# transformerless_5v_AC-DC_reulator.net
KiCad netlist of a schematic drawn in EAGLE
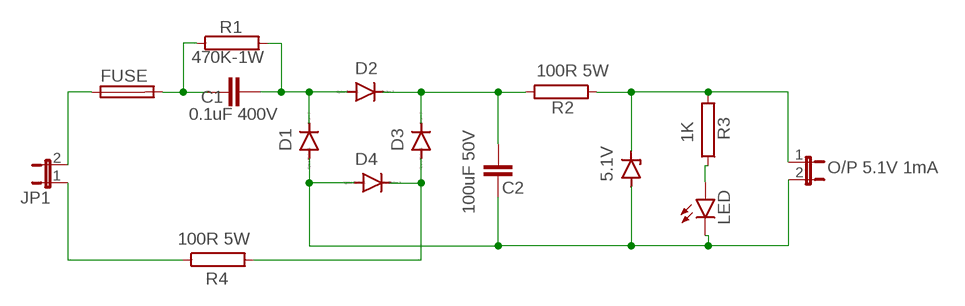
[diagram p0: schematic, sheet 1]

(export (version "E")
  (design (tool "Eeschema 10.0.6"))
  (components
    (comp (ref "C1")
      (value "0.1uF 400V")
      (footprint "eagle-import:C2.5-3")
      (libsource (lib "eagle-import") (part "C2,5-3"))
    )
    (comp (ref "C2")
      (value "100uF 50V")
      (footprint "eagle-import:C2.5-3")
      (libsource (lib "eagle-import") (part "C2,5-3"))
    )
    (comp (ref "D1")
      (value "1N4004")
      (footprint "eagle-import:DO41-10")
      (libsource (lib "eagle-import") (part "1N4004"))
    )
    (comp (ref "D2")
      (value "1N4004")
      (footprint "eagle-import:DO41-10")
      (libsource (lib "eagle-import") (part "1N4004"))
    )
    (comp (ref "D3")
      (value "1N4004")
      (footprint "eagle-import:DO41-10")
      (libsource (lib "eagle-import") (part "1N4004"))
    )
    (comp (ref "D4")
      (value "1N4004")
      (footprint "eagle-import:DO41-10")
      (libsource (lib "eagle-import") (part "1N4004"))
    )
    (comp (ref "FUSE")
      (value "GSH15")
      (footprint "eagle-import:GSH15")
      (fields (field (name "MPN") "64900001039"))
      (libsource (lib "eagle-import") (part "GSH15"))
    )
    (comp (ref "JP1")
      (value "JP1E")
      (footprint "eagle-import:JP1")
      (libsource (lib "eagle-import") (part "JP1E"))
    )
    (comp (ref "LED")
      (value "LED")
      (footprint "eagle-import:SMARTLED-TTW")
      (libsource (lib "eagle-import") (part "LED"))
    )
    (comp (ref "O/P")
      (value "O/P 5.1V 1mA")
      (footprint "eagle-import:JP1")
      (libsource (lib "eagle-import") (part "JP1E"))
    )
    (comp (ref "R1")
      (value "470K-1W")
      (footprint "eagle-import:AC01")
      (libsource (lib "eagle-import") (part "RAC01"))
    )
    (comp (ref "R2")
      (value "100R 5W")
      (footprint "eagle-import:AC01")
      (libsource (lib "eagle-import") (part "RAC01"))
    )
    (comp (ref "R3")
      (value "1K")
      (footprint "eagle-import:AC01")
      (libsource (lib "eagle-import") (part "RAC01"))
    )
    (comp (ref "R4")
      (value "100R 5W")
      (footprint "eagle-import:AC01")
      (libsource (lib "eagle-import") (part "RAC01"))
    )
    (comp (ref "ZENER")
      (value "5.1V")
      (footprint "eagle-import:DO35Z10")
      (libsource (lib "eagle-import") (part "ZPD"))
    )
  )
  (nets
    (net (code "1") (name "Net-(C1-Pad1)") (class "Default")
      (node (ref "C1") (pin "1") (pinfunction "1_1") (pintype "passive"))
      (node (ref "FUSE") (pin "2") (pinfunction "2_2") (pintype "passive"))
      (node (ref "R1") (pin "1") (pinfunction "1_1") (pintype "passive"))
    )
    (net (code "2") (name "Net-(C1-Pad2)") (class "Default")
      (node (ref "C1") (pin "2") (pinfunction "2_2") (pintype "passive"))
      (node (ref "D1") (pin "C") (pinfunction "C_C") (pintype "passive"))
      (node (ref "D2") (pin "A") (pinfunction "A_A") (pintype "passive"))
      (node (ref "R1") (pin "2") (pinfunction "2_2") (pintype "passive"))
    )
    (net (code "3") (name "Net-(C2-Pad1)") (class "Default")
      (node (ref "C2") (pin "1") (pinfunction "1_1") (pintype "passive"))
      (node (ref "D2") (pin "C") (pinfunction "C_C") (pintype "passive"))
      (node (ref "D3") (pin "C") (pinfunction "C_C") (pintype "passive"))
      (node (ref "R2") (pin "2") (pinfunction "2_2") (pintype "passive"))
    )
    (net (code "4") (name "Net-(D3-PadA)") (class "Default")
      (node (ref "D3") (pin "A") (pinfunction "A_A") (pintype "passive"))
      (node (ref "D4") (pin "C") (pinfunction "C_C") (pintype "passive"))
      (node (ref "R4") (pin "2") (pinfunction "2_2") (pintype "passive"))
    )
    (net (code "5") (name "Net-(FUSE-Pad1)") (class "Default")
      (node (ref "FUSE") (pin "1") (pinfunction "1_1") (pintype "passive"))
      (node (ref "JP1") (pin "2") (pinfunction "2_2") (pintype "passive"))
    )
    (net (code "6") (name "Net-(JP1-Pad1)") (class "Default")
      (node (ref "JP1") (pin "1") (pinfunction "1_1") (pintype "passive"))
      (node (ref "R4") (pin "1") (pinfunction "1_1") (pintype "passive"))
    )
    (net (code "7") (name "Net-(LED-A)") (class "Default")
      (node (ref "LED") (pin "A@1") (pinfunction "A_A@1") (pintype "passive"))
      (node (ref "R3") (pin "1") (pinfunction "1_1") (pintype "passive"))
    )
    (net (code "8") (name "Net-(LED-C)") (class "Default")
      (node (ref "C2") (pin "2") (pinfunction "2_2") (pintype "passive"))
      (node (ref "D1") (pin "A") (pinfunction "A_A") (pintype "passive"))
      (node (ref "D4") (pin "A") (pinfunction "A_A") (pintype "passive"))
      (node (ref "LED") (pin "C@1") (pinfunction "C_C@1") (pintype "passive"))
      (node (ref "O/P") (pin "2") (pinfunction "2_2") (pintype "passive"))
      (node (ref "ZENER") (pin "A") (pinfunction "A_A") (pintype "passive"))
    )
    (net (code "9") (name "Net-(O/P-Pad1)") (class "Default")
      (node (ref "O/P") (pin "1") (pinfunction "1_1") (pintype "passive"))
      (node (ref "R2") (pin "1") (pinfunction "1_1") (pintype "passive"))
      (node (ref "R3") (pin "2") (pinfunction "2_2") (pintype "passive"))
      (node (ref "ZENER") (pin "C") (pinfunction "C_C") (pintype "passive"))
    )
  )
)
